# ESP32W_Zzed.net
KiCad netlist of a schematic drawn in Altium Designer
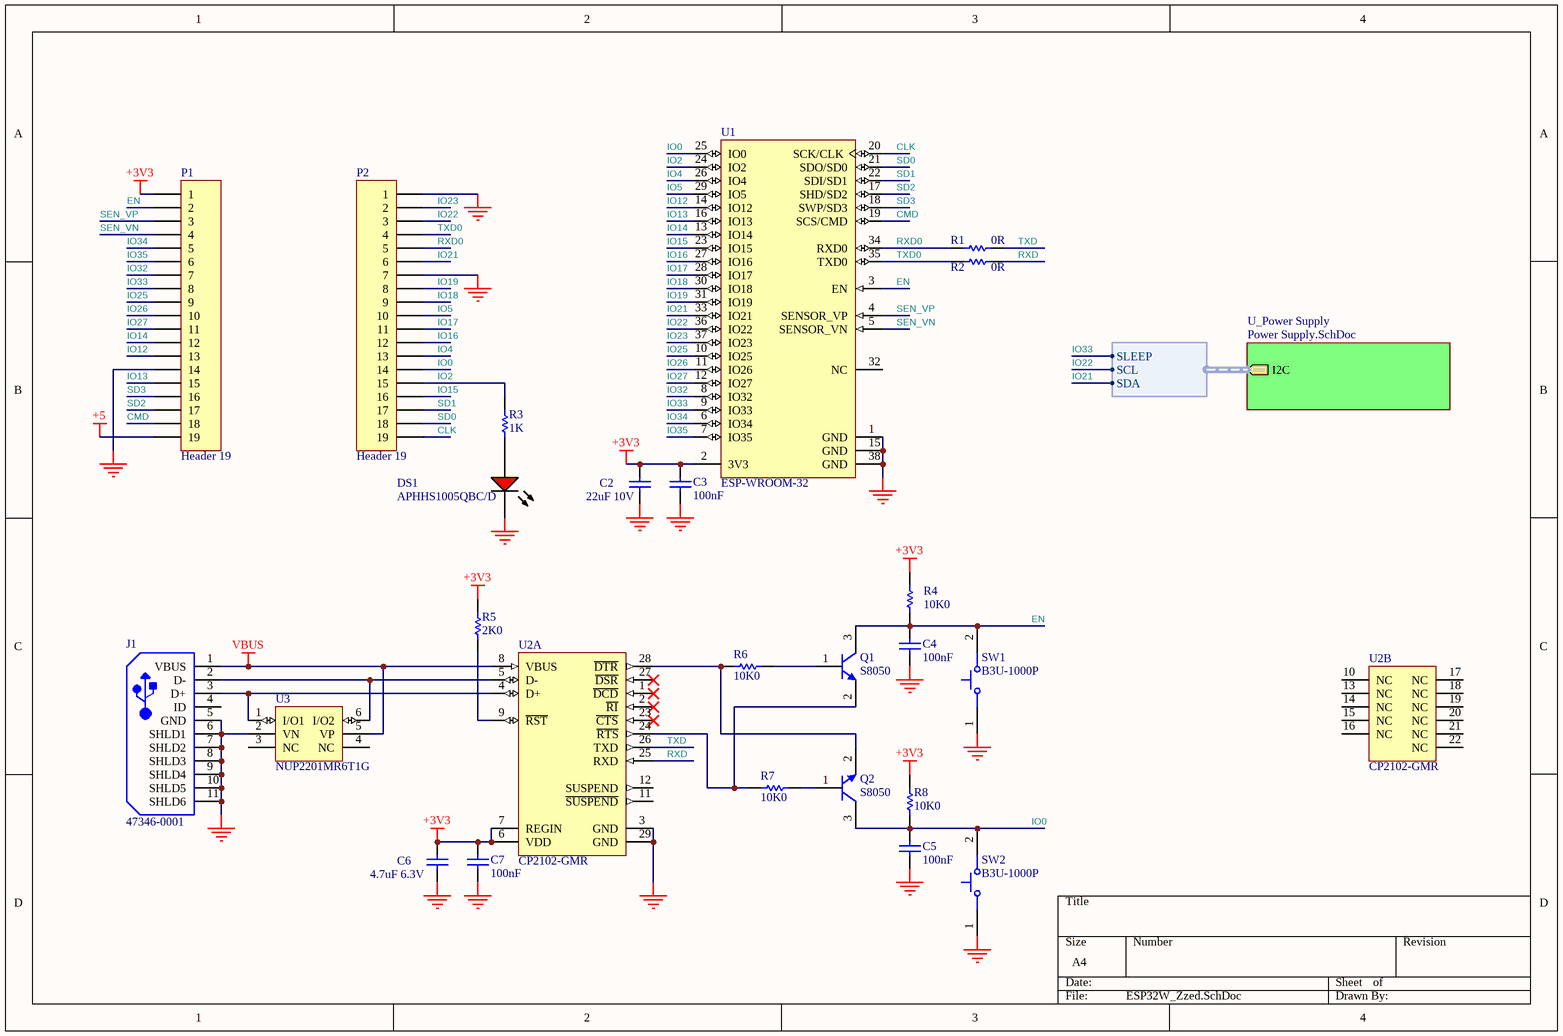
[diagram p0: ESP32W_Zzed.SchDoc]

(export (version "E")
  (design (tool "Eeschema 10.0.6"))
  (components
    (comp (ref "C2")
      (value "22uF 10V")
      (footprint "CAPC0805(2012)145_L")
      (description "CAP 22uF 10V ±10% 0805 (2012 Metric) Thickness 1.45mm SMD")
      (fields (field (name "TOLERANCE") "Â±10%"))
      (libsource (lib "Altium Content Vault") (part "CAP"))
    )
    (comp (ref "C3")
      (value "100nF")
      (footprint "CAPC0402(1005)60_L")
      (description "CAP 100nF 50V ±10% 0402 (1005 Metric) Thickness 0.6mm SMD")
      (fields (field (name "TOLERANCE") "Â±10%"))
      (libsource (lib "Altium Content Vault") (part "CAP"))
    )
    (comp (ref "C4")
      (value "100nF")
      (footprint "CAPC0402(1005)60_L")
      (description "CAP 100nF 50V ±10% 0402 (1005 Metric) Thickness 0.6mm SMD")
      (fields (field (name "TOLERANCE") "Â±10%"))
      (libsource (lib "Altium Content Vault") (part "CAP"))
    )
    (comp (ref "C5")
      (value "100nF")
      (footprint "CAPC0402(1005)60_L")
      (description "CAP 100nF 50V ±10% 0402 (1005 Metric) Thickness 0.6mm SMD")
      (fields (field (name "TOLERANCE") "Â±10%"))
      (libsource (lib "Altium Content Vault") (part "CAP"))
    )
    (comp (ref "C6")
      (value "4.7uF 6.3V")
      (footprint "CAPC0402(1005)60_L")
      (description "CAP 4.7uF 6.3V ±20% 0402 (1005 Metric) Thickness 0.6mm SMD")
      (fields (field (name "TOLERANCE") "Â±20%"))
      (libsource (lib "Altium Content Vault") (part "CAP"))
    )
    (comp (ref "C7")
      (value "100nF")
      (footprint "CAPC0402(1005)60_L")
      (description "CAP 100nF 50V ±10% 0402 (1005 Metric) Thickness 0.6mm SMD")
      (fields (field (name "TOLERANCE") "Â±10%"))
      (libsource (lib "Altium Content Vault") (part "CAP"))
    )
    (comp (ref "DS1")
      (value "APHHS1005QBC/D")
      (footprint "KING-0402_V")
      (fields (field (name "MANUFACTURER") "Kingbright"))
      (libsource (lib "Pathfinder") (part "LED-RED-AK-2"))
    )
    (comp (ref "J1")
      (value "47346-0001")
      (footprint "MOLX-47346-0001-5_V")
      (description "Micro-USB B Receptacle with Flange, -30 to 85 degC, 5-Pin SMD, RoHS, Tape and Reel")
      (fields (field (name "MANUFACTURER") "Molex"))
      (libsource (lib "Altium Content Vault") (part "MOLX-47346-0001-5"))
    )
    (comp (ref "P1")
      (value "Header 19")
      (footprint "HDR1X19")
      (description "Header, 19-Pin")
      (fields (field (name "PUBLISHER") "Altium Limited"))
      (libsource (lib "Miscellaneous Connectors") (part "Header 19"))
    )
    (comp (ref "P2")
      (value "Header 19")
      (footprint "HDR1X19")
      (description "Header, 19-Pin")
      (fields (field (name "PUBLISHER") "Altium Limited"))
      (libsource (lib "") (part "Header 19_1"))
    )
    (comp (ref "Q1")
      (value "S8050")
      (footprint "KOCN-SOT23-3_L")
      (description "NPN Transistor, 0.8 A Collector Current, 3-Pin SOT23, RoHS, Tape and Reel")
      (fields (field (name "MANUFACTURER") "Koo Chin"))
      (libsource (lib "Altium Content Vault") (part "KOCN-NPN-B1E2C3-3"))
    )
    (comp (ref "Q2")
      (value "S8050")
      (footprint "KOCN-SOT23-3_L")
      (description "NPN Transistor, 0.8 A Collector Current, 3-Pin SOT23, RoHS, Tape and Reel")
      (fields (field (name "MANUFACTURER") "Koo Chin"))
      (libsource (lib "Altium Content Vault") (part "KOCN-NPN-B1E2C3-3"))
    )
    (comp (ref "R1")
      (value "0R")
      (footprint "RESC0402(1005)_L")
      (description "Jumper 0402 (1005 Metric)")
      (fields (field (name "TOLERANCE") "None"))
      (libsource (lib "Altium Content Vault") (part "RES"))
    )
    (comp (ref "R2")
      (value "0R")
      (footprint "RESC0402(1005)_L")
      (description "Jumper 0402 (1005 Metric)")
      (fields (field (name "TOLERANCE") "None"))
      (libsource (lib "Altium Content Vault") (part "RES"))
    )
    (comp (ref "R3")
      (value "1K")
      (footprint "RESC0402(1005)_L")
      (description "1K 0.063W 1% 0402 (1005 Metric)  SMD")
      (fields (field (name "TOLERANCE") "1 %") (field (name "POWER") "0.063 W"))
      (libsource (lib "Altium Content Vault") (part "RES"))
    )
    (comp (ref "R4")
      (value "10K0")
      (footprint "RESC0402(1005)_L")
      (description "10K 0.063W 1% 0402 (1005 Metric)  SMD")
      (fields (field (name "TOLERANCE") "1 %") (field (name "POWER") "0.063 W"))
      (libsource (lib "Altium Content Vault") (part "RES"))
    )
    (comp (ref "R5")
      (value "2K0")
      (footprint "RESC0402(1005)_L")
      (description "2K 0.063W 1% 0402 (1005 Metric)  SMD")
      (fields (field (name "POWER") "0.063 W") (field (name "TOLERANCE") "1 %"))
      (libsource (lib "Altium Content Vault") (part "RES"))
    )
    (comp (ref "R6")
      (value "10K0")
      (footprint "RESC0402(1005)_L")
      (description "10K 0.063W 1% 0402 (1005 Metric)  SMD")
      (fields (field (name "TOLERANCE") "1 %") (field (name "POWER") "0.063 W"))
      (libsource (lib "Altium Content Vault") (part "RES"))
    )
    (comp (ref "R7")
      (value "10K0")
      (footprint "RESC0402(1005)_L")
      (description "10K 0.063W 1% 0402 (1005 Metric)  SMD")
      (fields (field (name "TOLERANCE") "1 %") (field (name "POWER") "0.063 W"))
      (libsource (lib "Altium Content Vault") (part "RES"))
    )
    (comp (ref "R8")
      (value "10K0")
      (footprint "RESC0402(1005)_L")
      (description "10K 0.063W 1% 0402 (1005 Metric)  SMD")
      (fields (field (name "TOLERANCE") "1 %") (field (name "POWER") "0.063 W"))
      (libsource (lib "Altium Content Vault") (part "RES"))
    )
    (comp (ref "SW1")
      (value "B3U-1000P")
      (footprint "OMRON-B3U-1000_V")
      (description "Ultra-Small Tactile Switch, 0.05 A, 12 V, -25 to 70 degC, 2-Pin SMD, RoHS, Tape and Reel")
      (fields (field (name "MANUFACTURER") "Omron Electronic Components"))
      (libsource (lib "Altium Content Vault") (part "SW-SPST-NO-2"))
    )
    (comp (ref "SW2")
      (value "B3U-1000P")
      (footprint "OMRON-B3U-1000_V")
      (description "Ultra-Small Tactile Switch, 0.05 A, 12 V, -25 to 70 degC, 2-Pin SMD, RoHS, Tape and Reel")
      (fields (field (name "MANUFACTURER") "Omron Electronic Components"))
      (libsource (lib "Altium Content Vault") (part "SW-SPST-NO-2"))
    )
    (comp (ref "U1")
      (value "ESP-WROOM-32")
      (footprint "OLMX-ESP-WROOM-32")
      (description "Espressif System, 2.7 to 3.6 V, -40 to 85 degC, 38-Pin SMD")
      (fields (field (name "MANUFACTURER") "Olimex"))
      (libsource (lib "Altium Content Vault") (part "OLMX-ESP-WROOM-32-38"))
    )
    (comp (ref "U2")
      (value "CP2102-GMR")
      (footprint "SLAB-QFN-28-3125x3125TP_N")
      (description "Single-Chip USB to URAT Bridge, 3.3 V, -40 to 85 degC, 28-Pin QFN, RoHS, Tape and Reel")
      (fields (field (name "MANUFACTURER") "Silicon Labs"))
      (libsource (lib "Altium Content Vault") (part "SLAB-CP210X-QFN-28-29"))
    )
    (comp (ref "U3")
      (value "NUP2201MR6T1G")
      (footprint "ONSC-TSOP-6_V")
      (description "ESD Protection Diodes with Low Clamping Voltage")
      (libsource (lib "Altium Content Vault") (part "ONSC-NUP2201MR6-TSOP-6"))
    )
  )
  (nets
    (net (code "2") (name "+3V3") (class "Default")
      (node (ref "C2") (pin "2") (pinfunction "2_2") (pintype "passive"))
      (node (ref "C3") (pin "2") (pinfunction "2_2") (pintype "passive"))
      (node (ref "C6") (pin "2") (pinfunction "2_2") (pintype "passive"))
      (node (ref "C7") (pin "2") (pinfunction "2_2") (pintype "passive"))
      (node (ref "P1") (pin "1") (pinfunction "1_1") (pintype "passive"))
      (node (ref "R4") (pin "2") (pinfunction "2_2") (pintype "passive"))
      (node (ref "R5") (pin "2") (pinfunction "2_2") (pintype "passive"))
      (node (ref "R8") (pin "1") (pinfunction "1_1") (pintype "passive"))
      (node (ref "U1") (pin "2") (pinfunction "3V3_2") (pintype "power_in"))
      (node (ref "U2") (pin "6") (pinfunction "VDD_6") (pintype "power_in"))
      (node (ref "U2") (pin "7") (pinfunction "REGIN_7") (pintype "power_in"))
    )
    (net (code "3") (name "+5") (class "Default")
      (node (ref "P1") (pin "19") (pinfunction "19_19") (pintype "passive"))
    )
    (net (code "4") (name "/CLK") (class "Default")
      (node (ref "P2") (pin "19") (pinfunction "19_19") (pintype "passive"))
      (node (ref "U1") (pin "20") (pinfunction "SCK/CLK_20") (pintype "bidirectional"))
    )
    (net (code "5") (name "/CMD") (class "Default")
      (node (ref "P1") (pin "18") (pinfunction "18_18") (pintype "passive"))
      (node (ref "U1") (pin "19") (pinfunction "SCS/CMD_19") (pintype "bidirectional"))
    )
    (net (code "6") (name "/EN") (class "Default")
      (node (ref "C4") (pin "2") (pinfunction "2_2") (pintype "passive"))
      (node (ref "P1") (pin "2") (pinfunction "2_2") (pintype "passive"))
      (node (ref "Q1") (pin "3") (pinfunction "COLLECTOR_3") (pintype "passive"))
      (node (ref "R4") (pin "1") (pinfunction "1_1") (pintype "passive"))
      (node (ref "SW1") (pin "2") (pinfunction "2_2") (pintype "passive"))
      (node (ref "U1") (pin "3") (pinfunction "EN_3") (pintype "input"))
    )
    (net (code "7") (name "/IO0") (class "Default")
      (node (ref "C5") (pin "2") (pinfunction "2_2") (pintype "passive"))
      (node (ref "P2") (pin "14") (pinfunction "14_14") (pintype "passive"))
      (node (ref "Q2") (pin "3") (pinfunction "COLLECTOR_3") (pintype "passive"))
      (node (ref "R8") (pin "2") (pinfunction "2_2") (pintype "passive"))
      (node (ref "SW2") (pin "2") (pinfunction "2_2") (pintype "passive"))
      (node (ref "U1") (pin "25") (pinfunction "IO0_25") (pintype "bidirectional"))
    )
    (net (code "8") (name "/IO2") (class "Default")
      (node (ref "P2") (pin "15") (pinfunction "15_15") (pintype "passive"))
      (node (ref "R3") (pin "2") (pinfunction "2_2") (pintype "passive"))
      (node (ref "U1") (pin "24") (pinfunction "IO2_24") (pintype "bidirectional"))
    )
    (net (code "9") (name "/IO4") (class "Default")
      (node (ref "P2") (pin "13") (pinfunction "13_13") (pintype "passive"))
      (node (ref "U1") (pin "26") (pinfunction "IO4_26") (pintype "bidirectional"))
    )
    (net (code "10") (name "/IO5") (class "Default")
      (node (ref "P2") (pin "10") (pinfunction "10_10") (pintype "passive"))
      (node (ref "U1") (pin "29") (pinfunction "IO5_29") (pintype "bidirectional"))
    )
    (net (code "11") (name "/IO12") (class "Default")
      (node (ref "P1") (pin "13") (pinfunction "13_13") (pintype "passive"))
      (node (ref "U1") (pin "14") (pinfunction "IO12_14") (pintype "bidirectional"))
    )
    (net (code "12") (name "/IO13") (class "Default")
      (node (ref "P1") (pin "15") (pinfunction "15_15") (pintype "passive"))
      (node (ref "U1") (pin "16") (pinfunction "IO13_16") (pintype "bidirectional"))
    )
    (net (code "13") (name "/IO14") (class "Default")
      (node (ref "P1") (pin "12") (pinfunction "12_12") (pintype "passive"))
      (node (ref "U1") (pin "13") (pinfunction "IO14_13") (pintype "bidirectional"))
    )
    (net (code "14") (name "/IO15") (class "Default")
      (node (ref "P2") (pin "16") (pinfunction "16_16") (pintype "passive"))
      (node (ref "U1") (pin "23") (pinfunction "IO15_23") (pintype "bidirectional"))
    )
    (net (code "15") (name "/IO16") (class "Default")
      (node (ref "P2") (pin "12") (pinfunction "12_12") (pintype "passive"))
      (node (ref "U1") (pin "27") (pinfunction "IO16_27") (pintype "bidirectional"))
    )
    (net (code "16") (name "/IO17") (class "Default")
      (node (ref "P2") (pin "11") (pinfunction "11_11") (pintype "passive"))
      (node (ref "U1") (pin "28") (pinfunction "IO17_28") (pintype "bidirectional"))
    )
    (net (code "17") (name "/IO18") (class "Default")
      (node (ref "P2") (pin "9") (pinfunction "9_9") (pintype "passive"))
      (node (ref "U1") (pin "30") (pinfunction "IO18_30") (pintype "bidirectional"))
    )
    (net (code "18") (name "/IO19") (class "Default")
      (node (ref "P2") (pin "8") (pinfunction "8_8") (pintype "passive"))
      (node (ref "U1") (pin "31") (pinfunction "IO19_31") (pintype "bidirectional"))
    )
    (net (code "19") (name "/IO21") (class "Default")
      (node (ref "P2") (pin "6") (pinfunction "6_6") (pintype "passive"))
      (node (ref "U1") (pin "33") (pinfunction "IO21_33") (pintype "bidirectional"))
    )
    (net (code "20") (name "/IO22") (class "Default")
      (node (ref "P2") (pin "3") (pinfunction "3_3") (pintype "passive"))
      (node (ref "U1") (pin "36") (pinfunction "IO22_36") (pintype "bidirectional"))
    )
    (net (code "21") (name "/IO23") (class "Default")
      (node (ref "P2") (pin "2") (pinfunction "2_2") (pintype "passive"))
      (node (ref "U1") (pin "37") (pinfunction "IO23_37") (pintype "bidirectional"))
    )
    (net (code "22") (name "/IO25") (class "Default")
      (node (ref "P1") (pin "9") (pinfunction "9_9") (pintype "passive"))
      (node (ref "U1") (pin "10") (pinfunction "IO25_10") (pintype "bidirectional"))
    )
    (net (code "23") (name "/IO26") (class "Default")
      (node (ref "P1") (pin "10") (pinfunction "10_10") (pintype "passive"))
      (node (ref "U1") (pin "11") (pinfunction "IO26_11") (pintype "bidirectional"))
    )
    (net (code "24") (name "/IO27") (class "Default")
      (node (ref "P1") (pin "11") (pinfunction "11_11") (pintype "passive"))
      (node (ref "U1") (pin "12") (pinfunction "IO27_12") (pintype "bidirectional"))
    )
    (net (code "25") (name "/IO32") (class "Default")
      (node (ref "P1") (pin "7") (pinfunction "7_7") (pintype "passive"))
      (node (ref "U1") (pin "8") (pinfunction "IO32_8") (pintype "bidirectional"))
    )
    (net (code "26") (name "/IO33") (class "Default")
      (node (ref "P1") (pin "8") (pinfunction "8_8") (pintype "passive"))
      (node (ref "U1") (pin "9") (pinfunction "IO33_9") (pintype "bidirectional"))
    )
    (net (code "27") (name "/IO34") (class "Default")
      (node (ref "P1") (pin "5") (pinfunction "5_5") (pintype "passive"))
      (node (ref "U1") (pin "6") (pinfunction "IO34_6") (pintype "bidirectional"))
    )
    (net (code "28") (name "/IO35") (class "Default")
      (node (ref "P1") (pin "6") (pinfunction "6_6") (pintype "passive"))
      (node (ref "U1") (pin "7") (pinfunction "IO35_7") (pintype "bidirectional"))
    )
    (net (code "29") (name "/RXD") (class "Default")
      (node (ref "R2") (pin "2") (pinfunction "2_2") (pintype "passive"))
      (node (ref "U2") (pin "25") (pinfunction "RXD_25") (pintype "input"))
    )
    (net (code "30") (name "/RXD0") (class "Default")
      (node (ref "P2") (pin "5") (pinfunction "5_5") (pintype "passive"))
      (node (ref "R1") (pin "1") (pinfunction "1_1") (pintype "passive"))
      (node (ref "U1") (pin "34") (pinfunction "RXD0_34") (pintype "bidirectional"))
    )
    (net (code "31") (name "/SD0") (class "Default")
      (node (ref "P2") (pin "18") (pinfunction "18_18") (pintype "passive"))
      (node (ref "U1") (pin "21") (pinfunction "SDO/SD0_21") (pintype "bidirectional"))
    )
    (net (code "32") (name "/SD1") (class "Default")
      (node (ref "P2") (pin "17") (pinfunction "17_17") (pintype "passive"))
      (node (ref "U1") (pin "22") (pinfunction "SDI/SD1_22") (pintype "bidirectional"))
    )
    (net (code "33") (name "/SD2") (class "Default")
      (node (ref "P1") (pin "17") (pinfunction "17_17") (pintype "passive"))
      (node (ref "U1") (pin "17") (pinfunction "SHD/SD2_17") (pintype "bidirectional"))
    )
    (net (code "34") (name "/SD3") (class "Default")
      (node (ref "P1") (pin "16") (pinfunction "16_16") (pintype "passive"))
      (node (ref "U1") (pin "18") (pinfunction "SWP/SD3_18") (pintype "bidirectional"))
    )
    (net (code "35") (name "/SEN_VN") (class "Default")
      (node (ref "P1") (pin "4") (pinfunction "4_4") (pintype "passive"))
      (node (ref "U1") (pin "5") (pinfunction "SENSOR_VN_5") (pintype "input"))
    )
    (net (code "36") (name "/SEN_VP") (class "Default")
      (node (ref "P1") (pin "3") (pinfunction "3_3") (pintype "passive"))
      (node (ref "U1") (pin "4") (pinfunction "SENSOR_VP_4") (pintype "input"))
    )
    (net (code "37") (name "/TXD") (class "Default")
      (node (ref "R1") (pin "2") (pinfunction "2_2") (pintype "passive"))
      (node (ref "U2") (pin "26") (pinfunction "TXD_26") (pintype "output"))
    )
    (net (code "38") (name "/TXD0") (class "Default")
      (node (ref "P2") (pin "4") (pinfunction "4_4") (pintype "passive"))
      (node (ref "R2") (pin "1") (pinfunction "1_1") (pintype "passive"))
      (node (ref "U1") (pin "35") (pinfunction "TXD0_35") (pintype "bidirectional"))
    )
    (net (code "40") (name "GND") (class "Default")
      (node (ref "C2") (pin "1") (pinfunction "1_1") (pintype "passive"))
      (node (ref "C3") (pin "1") (pinfunction "1_1") (pintype "passive"))
      (node (ref "C4") (pin "1") (pinfunction "1_1") (pintype "passive"))
      (node (ref "C5") (pin "1") (pinfunction "1_1") (pintype "passive"))
      (node (ref "C6") (pin "1") (pinfunction "1_1") (pintype "passive"))
      (node (ref "C7") (pin "1") (pinfunction "1_1") (pintype "passive"))
      (node (ref "DS1") (pin "2") (pinfunction "K_2") (pintype "passive"))
      (node (ref "J1") (pin "10") (pinfunction "SHLD5_10") (pintype "passive"))
      (node (ref "J1") (pin "11") (pinfunction "SHLD6_11") (pintype "passive"))
      (node (ref "J1") (pin "5") (pinfunction "GND_5") (pintype "passive"))
      (node (ref "J1") (pin "6") (pinfunction "SHLD1_6") (pintype "passive"))
      (node (ref "J1") (pin "7") (pinfunction "SHLD2_7") (pintype "passive"))
      (node (ref "J1") (pin "8") (pinfunction "SHLD3_8") (pintype "passive"))
      (node (ref "J1") (pin "9") (pinfunction "SHLD4_9") (pintype "passive"))
      (node (ref "P1") (pin "14") (pinfunction "14_14") (pintype "passive"))
      (node (ref "P2") (pin "1") (pinfunction "1_1") (pintype "passive"))
      (node (ref "P2") (pin "7") (pinfunction "7_7") (pintype "passive"))
      (node (ref "SW1") (pin "1") (pinfunction "1_1") (pintype "passive"))
      (node (ref "SW2") (pin "1") (pinfunction "1_1") (pintype "passive"))
      (node (ref "U1") (pin "1") (pinfunction "GND_1") (pintype "power_in"))
      (node (ref "U1") (pin "15") (pinfunction "GND_15") (pintype "power_in"))
      (node (ref "U1") (pin "38") (pinfunction "GND_38") (pintype "power_in"))
      (node (ref "U2") (pin "29") (pinfunction "GND_29") (pintype "power_in"))
      (node (ref "U2") (pin "3") (pinfunction "GND_3") (pintype "power_in"))
      (node (ref "U3") (pin "2") (pinfunction "VN_2") (pintype "power_in"))
    )
    (net (code "41") (name "Net-(DS1-A)") (class "Default")
      (node (ref "DS1") (pin "1") (pinfunction "A_1") (pintype "passive"))
      (node (ref "R3") (pin "1") (pinfunction "1_1") (pintype "passive"))
    )
    (net (code "42") (name "Net-(J1-D+)") (class "Default")
      (node (ref "J1") (pin "3") (pinfunction "D+_3") (pintype "passive"))
      (node (ref "U2") (pin "4") (pinfunction "D+_4") (pintype "bidirectional"))
      (node (ref "U3") (pin "1") (pinfunction "I/O1_1") (pintype "bidirectional"))
    )
    (net (code "43") (name "Net-(J1-D-)") (class "Default")
      (node (ref "J1") (pin "2") (pinfunction "D-_2") (pintype "passive"))
      (node (ref "U2") (pin "5") (pinfunction "D-_5") (pintype "bidirectional"))
      (node (ref "U3") (pin "6") (pinfunction "I/O2_6") (pintype "bidirectional"))
    )
    (net (code "44") (name "Net-(Q1-BASE)") (class "Default")
      (node (ref "Q1") (pin "1") (pinfunction "BASE_1") (pintype "passive"))
      (node (ref "R6") (pin "2") (pinfunction "2_2") (pintype "passive"))
    )
    (net (code "45") (name "Net-(Q1-EMITTER)") (class "Default")
      (node (ref "Q1") (pin "2") (pinfunction "EMITTER_2") (pintype "passive"))
      (node (ref "R7") (pin "1") (pinfunction "1_1") (pintype "passive"))
      (node (ref "U2") (pin "24") (pinfunction "~{RTS}_24") (pintype "output"))
    )
    (net (code "46") (name "Net-(Q2-BASE)") (class "Default")
      (node (ref "Q2") (pin "1") (pinfunction "BASE_1") (pintype "passive"))
      (node (ref "R7") (pin "2") (pinfunction "2_2") (pintype "passive"))
    )
    (net (code "47") (name "Net-(Q2-EMITTER)") (class "Default")
      (node (ref "Q2") (pin "2") (pinfunction "EMITTER_2") (pintype "passive"))
      (node (ref "R6") (pin "1") (pinfunction "1_1") (pintype "passive"))
      (node (ref "U2") (pin "28") (pinfunction "~{DTR}_28") (pintype "output"))
    )
    (net (code "48") (name "Net-(U2A-~{RST})") (class "Default")
      (node (ref "R5") (pin "1") (pinfunction "1_1") (pintype "passive"))
      (node (ref "U2") (pin "9") (pinfunction "~{RST}_9") (pintype "bidirectional"))
    )
    (net (code "49") (name "VBUS") (class "Default")
      (node (ref "J1") (pin "1") (pinfunction "VBUS_1") (pintype "passive"))
      (node (ref "U2") (pin "8") (pinfunction "VBUS_8") (pintype "input"))
      (node (ref "U3") (pin "5") (pinfunction "VP_5") (pintype "power_in"))
    )
    (net (code "50") (name "unconnected-(J1-ID-Pad4)") (class "Default")
      (node (ref "J1") (pin "4") (pinfunction "ID_4") (pintype "passive"))
    )
    (net (code "51") (name "unconnected-(U1-NC-Pad32)") (class "Default")
      (node (ref "U1") (pin "32") (pinfunction "NC_32") (pintype "passive"))
    )
    (net (code "52") (name "unconnected-(U2A-SUSPEND-Pad12)") (class "Default")
      (node (ref "U2") (pin "12") (pinfunction "SUSPEND_12") (pintype "output"))
    )
    (net (code "53") (name "unconnected-(U2A-~{CTS}-Pad23)") (class "Default")
      (node (ref "U2") (pin "23") (pinfunction "~{CTS}_23") (pintype "input+no_connect"))
    )
    (net (code "54") (name "unconnected-(U2A-~{DCD}-Pad1)") (class "Default")
      (node (ref "U2") (pin "1") (pinfunction "~{DCD}_1") (pintype "input+no_connect"))
    )
    (net (code "55") (name "unconnected-(U2A-~{DSR}-Pad27)") (class "Default")
      (node (ref "U2") (pin "27") (pinfunction "~{DSR}_27") (pintype "input+no_connect"))
    )
    (net (code "56") (name "unconnected-(U2A-~{RI}-Pad2)") (class "Default")
      (node (ref "U2") (pin "2") (pinfunction "~{RI}_2") (pintype "input+no_connect"))
    )
    (net (code "57") (name "unconnected-(U2A-~{SUSPEND}-Pad11)") (class "Default")
      (node (ref "U2") (pin "11") (pinfunction "~{SUSPEND}_11") (pintype "output"))
    )
    (net (code "58") (name "unconnected-(U2B-NC-Pad10)") (class "Default")
      (node (ref "U2") (pin "10") (pinfunction "NC_10") (pintype "passive"))
    )
    (net (code "59") (name "unconnected-(U2B-NC-Pad13)") (class "Default")
      (node (ref "U2") (pin "13") (pinfunction "NC_13") (pintype "passive"))
    )
    (net (code "60") (name "unconnected-(U2B-NC-Pad14)") (class "Default")
      (node (ref "U2") (pin "14") (pinfunction "NC_14") (pintype "passive"))
    )
    (net (code "61") (name "unconnected-(U2B-NC-Pad15)") (class "Default")
      (node (ref "U2") (pin "15") (pinfunction "NC_15") (pintype "passive"))
    )
    (net (code "62") (name "unconnected-(U2B-NC-Pad16)") (class "Default")
      (node (ref "U2") (pin "16") (pinfunction "NC_16") (pintype "passive"))
    )
    (net (code "63") (name "unconnected-(U2B-NC-Pad17)") (class "Default")
      (node (ref "U2") (pin "17") (pinfunction "NC_17") (pintype "passive"))
    )
    (net (code "64") (name "unconnected-(U2B-NC-Pad18)") (class "Default")
      (node (ref "U2") (pin "18") (pinfunction "NC_18") (pintype "passive"))
    )
    (net (code "65") (name "unconnected-(U2B-NC-Pad19)") (class "Default")
      (node (ref "U2") (pin "19") (pinfunction "NC_19") (pintype "passive"))
    )
    (net (code "66") (name "unconnected-(U2B-NC-Pad20)") (class "Default")
      (node (ref "U2") (pin "20") (pinfunction "NC_20") (pintype "passive"))
    )
    (net (code "67") (name "unconnected-(U2B-NC-Pad21)") (class "Default")
      (node (ref "U2") (pin "21") (pinfunction "NC_21") (pintype "passive"))
    )
    (net (code "68") (name "unconnected-(U2B-NC-Pad22)") (class "Default")
      (node (ref "U2") (pin "22") (pinfunction "NC_22") (pintype "passive"))
    )
    (net (code "69") (name "unconnected-(U3-NC-Pad3)") (class "Default")
      (node (ref "U3") (pin "3") (pinfunction "NC_3") (pintype "passive"))
    )
    (net (code "70") (name "unconnected-(U3-NC-Pad4)") (class "Default")
      (node (ref "U3") (pin "4") (pinfunction "NC_4") (pintype "passive"))
    )
  )
)
